# C64-Wifi_UserP.net
KiCad netlist of a schematic drawn in EAGLE
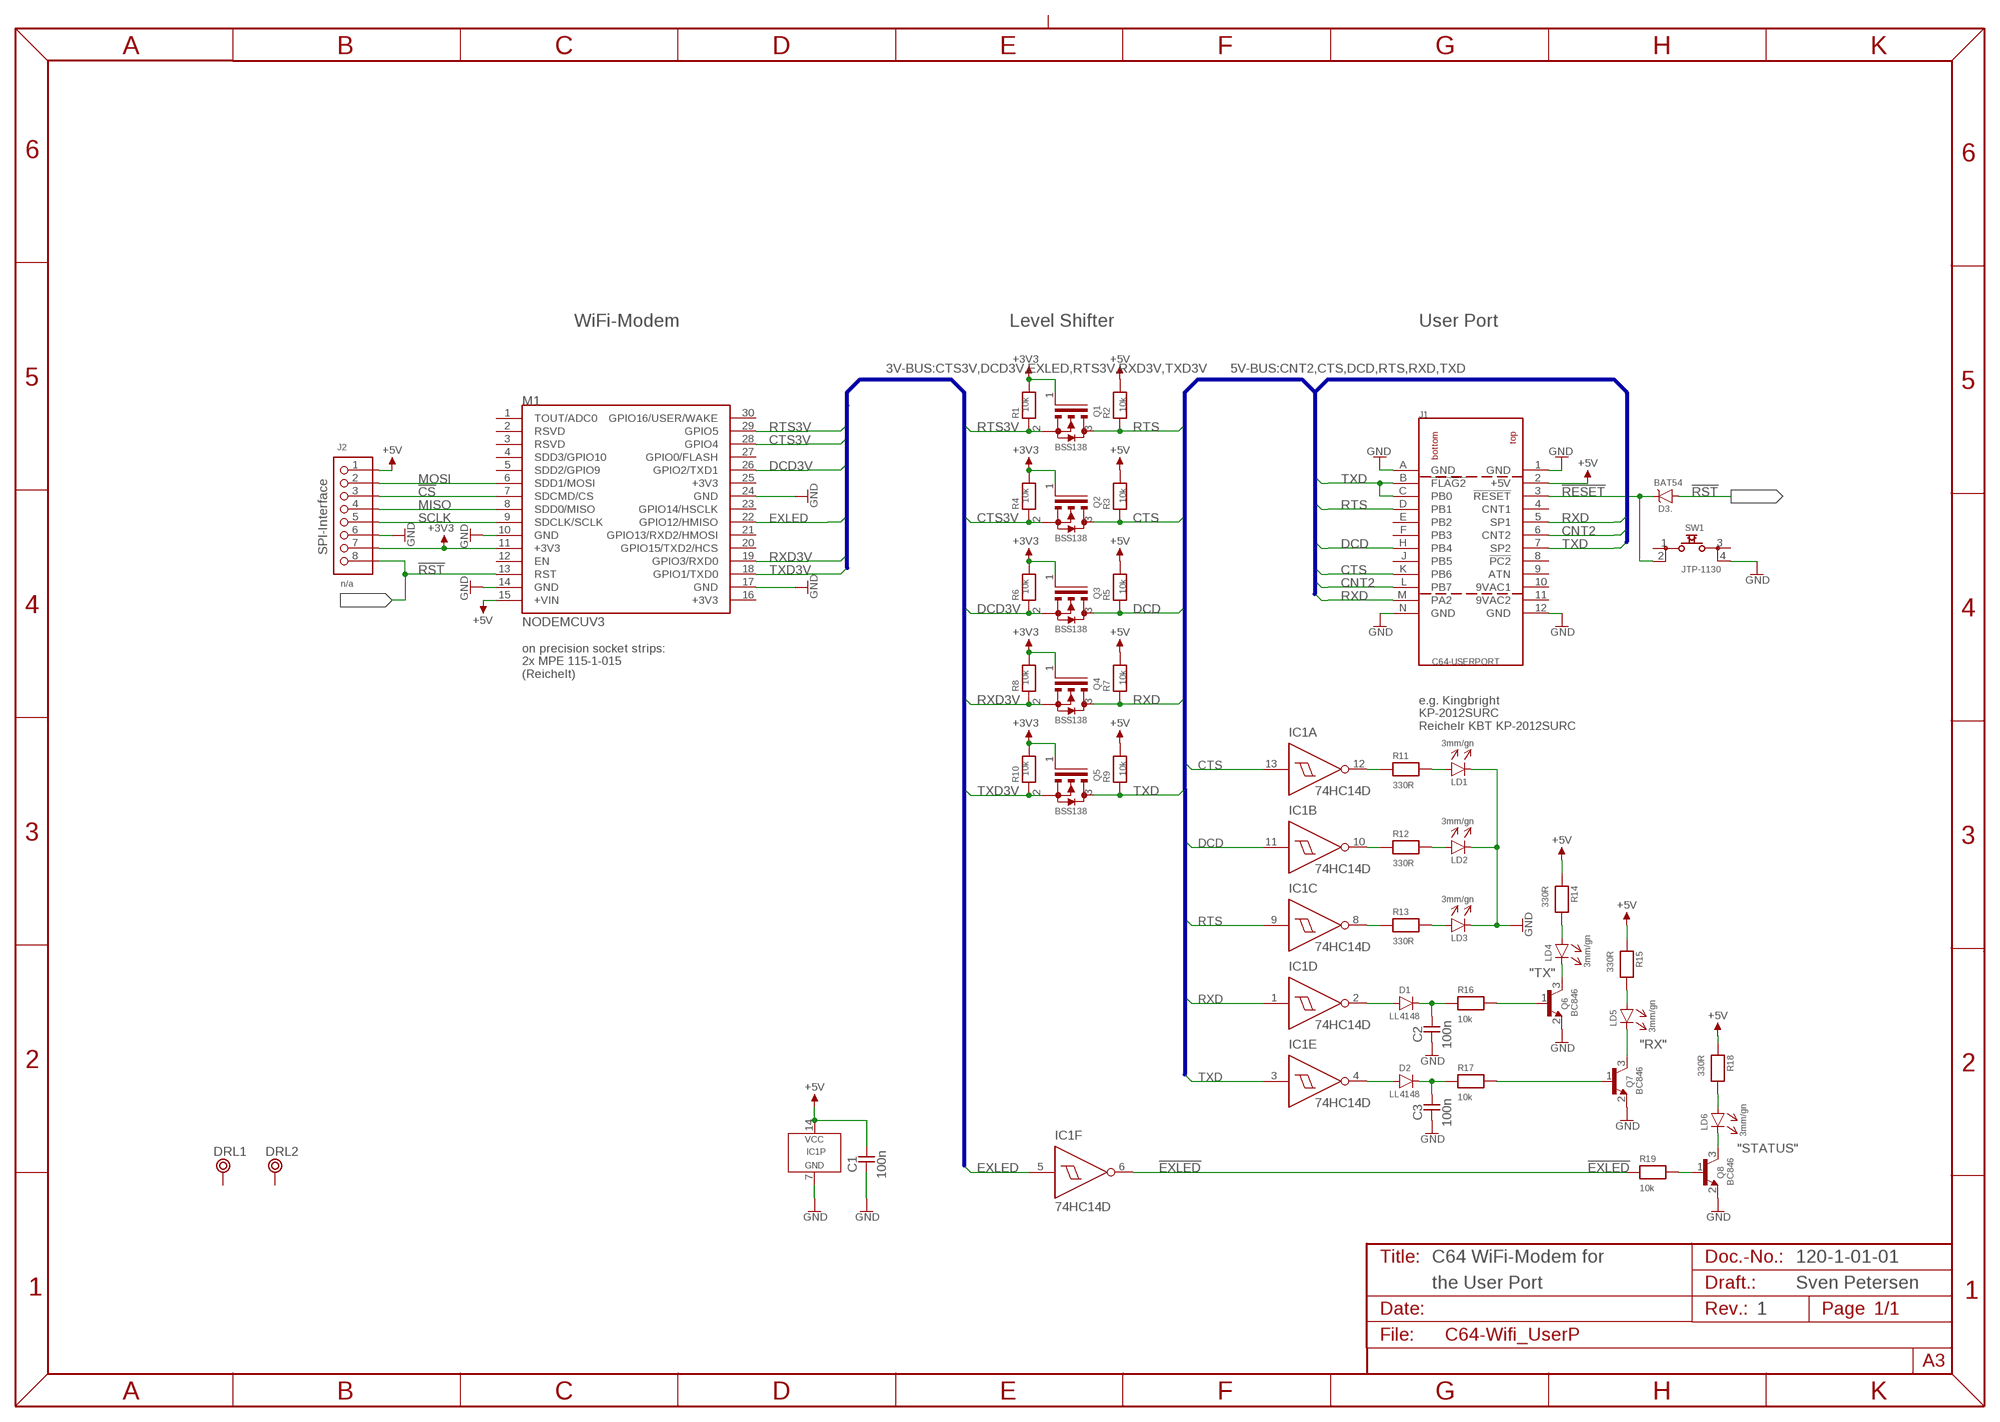
[diagram p0: schematic, sheet 1]

(export (version "E")
  (design (tool "Eeschema 10.0.6"))
  (components
    (comp (ref "C1")
      (value "100n")
      (footprint "eagle-import:0805")
      (libsource (lib "eagle-import") (part "C-0805"))
    )
    (comp (ref "C2")
      (value "100n")
      (footprint "eagle-import:0805")
      (libsource (lib "eagle-import") (part "C-0805"))
    )
    (comp (ref "C3")
      (value "100n")
      (footprint "eagle-import:0805")
      (libsource (lib "eagle-import") (part "C-0805"))
    )
    (comp (ref "D1")
      (value "LL4148")
      (footprint "eagle-import:SOD80C")
      (libsource (lib "eagle-import") (part "LL4148"))
    )
    (comp (ref "D2")
      (value "LL4148")
      (footprint "eagle-import:SOD80C")
      (libsource (lib "eagle-import") (part "LL4148"))
    )
    (comp (ref "D3")
      (value "BAT54")
      (footprint "eagle-import:SOT23")
      (libsource (lib "eagle-import") (part "D-BAT54"))
    )
    (comp (ref "DRL1")
      (value "BOHR3,3")
      (footprint "eagle-import:BOHR3,3")
      (libsource (lib "eagle-import") (part "BOHR3,3"))
    )
    (comp (ref "DRL2")
      (value "BOHR3,3")
      (footprint "eagle-import:BOHR3,3")
      (libsource (lib "eagle-import") (part "BOHR3,3"))
    )
    (comp (ref "IC1")
      (value "74HC14D")
      (footprint "eagle-import:SO-14")
      (libsource (lib "eagle-import") (part "7414"))
    )
    (comp (ref "J1")
      (value "C64-USERPORT")
      (footprint "eagle-import:USERPORT")
      (libsource (lib "eagle-import") (part "C64-USERPORT"))
    )
    (comp (ref "J2")
      (value "n/a")
      (footprint "eagle-import:1X08")
      (libsource (lib "eagle-import") (part "PINHD-1X8"))
    )
    (comp (ref "LD1")
      (value "3mm/gn")
      (footprint "eagle-import:3MM")
      (libsource (lib "eagle-import") (part "0805-LED3MM"))
    )
    (comp (ref "LD2")
      (value "3mm/gn")
      (footprint "eagle-import:3MM")
      (libsource (lib "eagle-import") (part "0805-LED3MM"))
    )
    (comp (ref "LD3")
      (value "3mm/gn")
      (footprint "eagle-import:3MM")
      (libsource (lib "eagle-import") (part "0805-LED3MM"))
    )
    (comp (ref "LD4")
      (value "3mm/gn")
      (footprint "eagle-import:3MM")
      (libsource (lib "eagle-import") (part "0805-LED3MM"))
    )
    (comp (ref "LD5")
      (value "3mm/gn")
      (footprint "eagle-import:3MM")
      (libsource (lib "eagle-import") (part "0805-LED3MM"))
    )
    (comp (ref "LD6")
      (value "3mm/gn")
      (footprint "eagle-import:3MM")
      (libsource (lib "eagle-import") (part "0805-LED3MM"))
    )
    (comp (ref "M1")
      (value "NODEMCUV3")
      (footprint "eagle-import:NODEMCUV3")
      (libsource (lib "eagle-import") (part "NODEMCUV3"))
    )
    (comp (ref "Q1")
      (value "BSS138")
      (footprint "eagle-import:SOT23")
      (libsource (lib "eagle-import") (part "BSS138"))
    )
    (comp (ref "Q2")
      (value "BSS138")
      (footprint "eagle-import:SOT23")
      (libsource (lib "eagle-import") (part "BSS138"))
    )
    (comp (ref "Q3")
      (value "BSS138")
      (footprint "eagle-import:SOT23")
      (libsource (lib "eagle-import") (part "BSS138"))
    )
    (comp (ref "Q4")
      (value "BSS138")
      (footprint "eagle-import:SOT23")
      (libsource (lib "eagle-import") (part "BSS138"))
    )
    (comp (ref "Q5")
      (value "BSS138")
      (footprint "eagle-import:SOT23")
      (libsource (lib "eagle-import") (part "BSS138"))
    )
    (comp (ref "Q6")
      (value "BC846")
      (footprint "eagle-import:SOT23")
      (libsource (lib "eagle-import") (part "BC846"))
    )
    (comp (ref "Q7")
      (value "BC846")
      (footprint "eagle-import:SOT23")
      (libsource (lib "eagle-import") (part "BC846"))
    )
    (comp (ref "Q8")
      (value "BC846")
      (footprint "eagle-import:SOT23")
      (libsource (lib "eagle-import") (part "BC846"))
    )
    (comp (ref "R1")
      (value "10k")
      (footprint "eagle-import:0805")
      (libsource (lib "eagle-import") (part "R-0805"))
    )
    (comp (ref "R2")
      (value "10k")
      (footprint "eagle-import:0805")
      (libsource (lib "eagle-import") (part "R-0805"))
    )
    (comp (ref "R3")
      (value "10k")
      (footprint "eagle-import:0805")
      (libsource (lib "eagle-import") (part "R-0805"))
    )
    (comp (ref "R4")
      (value "10k")
      (footprint "eagle-import:0805")
      (libsource (lib "eagle-import") (part "R-0805"))
    )
    (comp (ref "R5")
      (value "10k")
      (footprint "eagle-import:0805")
      (libsource (lib "eagle-import") (part "R-0805"))
    )
    (comp (ref "R6")
      (value "10k")
      (footprint "eagle-import:0805")
      (libsource (lib "eagle-import") (part "R-0805"))
    )
    (comp (ref "R7")
      (value "10k")
      (footprint "eagle-import:0805")
      (libsource (lib "eagle-import") (part "R-0805"))
    )
    (comp (ref "R8")
      (value "10k")
      (footprint "eagle-import:0805")
      (libsource (lib "eagle-import") (part "R-0805"))
    )
    (comp (ref "R9")
      (value "10k")
      (footprint "eagle-import:0805")
      (libsource (lib "eagle-import") (part "R-0805"))
    )
    (comp (ref "R10")
      (value "10k")
      (footprint "eagle-import:0805")
      (libsource (lib "eagle-import") (part "R-0805"))
    )
    (comp (ref "R11")
      (value "330R")
      (footprint "eagle-import:0805")
      (libsource (lib "eagle-import") (part "R-0805"))
    )
    (comp (ref "R12")
      (value "330R")
      (footprint "eagle-import:0805")
      (libsource (lib "eagle-import") (part "R-0805"))
    )
    (comp (ref "R13")
      (value "330R")
      (footprint "eagle-import:0805")
      (libsource (lib "eagle-import") (part "R-0805"))
    )
    (comp (ref "R14")
      (value "330R")
      (footprint "eagle-import:0805")
      (libsource (lib "eagle-import") (part "R-0805"))
    )
    (comp (ref "R15")
      (value "330R")
      (footprint "eagle-import:0805")
      (libsource (lib "eagle-import") (part "R-0805"))
    )
    (comp (ref "R16")
      (value "10k")
      (footprint "eagle-import:0805")
      (libsource (lib "eagle-import") (part "R-0805"))
    )
    (comp (ref "R17")
      (value "10k")
      (footprint "eagle-import:0805")
      (libsource (lib "eagle-import") (part "R-0805"))
    )
    (comp (ref "R18")
      (value "330R")
      (footprint "eagle-import:0805")
      (libsource (lib "eagle-import") (part "R-0805"))
    )
    (comp (ref "R19")
      (value "10k")
      (footprint "eagle-import:0805")
      (libsource (lib "eagle-import") (part "R-0805"))
    )
    (comp (ref "SW1")
      (value "JTP-1130")
      (footprint "eagle-import:JTP-1130")
      (libsource (lib "eagle-import") (part "JTP-1130"))
    )
  )
  (nets
    (net (code "3") (name "+3V3") (class "Default")
      (node (ref "J2") (pin "7") (pinfunction "7_7") (pintype "passive"))
      (node (ref "M1") (pin "11") (pinfunction "+3V3_11") (pintype "bidirectional"))
      (node (ref "Q1") (pin "1") (pinfunction "G_1") (pintype "bidirectional"))
      (node (ref "Q2") (pin "1") (pinfunction "G_1") (pintype "bidirectional"))
      (node (ref "Q3") (pin "1") (pinfunction "G_1") (pintype "bidirectional"))
      (node (ref "Q4") (pin "1") (pinfunction "G_1") (pintype "bidirectional"))
      (node (ref "Q5") (pin "1") (pinfunction "G_1") (pintype "bidirectional"))
      (node (ref "R1") (pin "2") (pinfunction "2_2") (pintype "passive"))
      (node (ref "R10") (pin "2") (pinfunction "2_2") (pintype "passive"))
      (node (ref "R4") (pin "2") (pinfunction "2_2") (pintype "passive"))
      (node (ref "R6") (pin "2") (pinfunction "2_2") (pintype "passive"))
      (node (ref "R8") (pin "2") (pinfunction "2_2") (pintype "passive"))
    )
    (net (code "4") (name "+5V") (class "Default")
      (node (ref "C1") (pin "2") (pinfunction "2_2") (pintype "passive"))
      (node (ref "IC1") (pin "14") (pinfunction "VCC_14") (pintype "bidirectional"))
      (node (ref "J1") (pin "2") (pinfunction "+5V_2") (pintype "power_in"))
      (node (ref "J2") (pin "1") (pinfunction "1_1") (pintype "passive"))
      (node (ref "M1") (pin "15") (pinfunction "+VIN_15") (pintype "bidirectional"))
      (node (ref "R14") (pin "1") (pinfunction "1_1") (pintype "passive"))
      (node (ref "R15") (pin "1") (pinfunction "1_1") (pintype "passive"))
      (node (ref "R18") (pin "1") (pinfunction "1_1") (pintype "passive"))
      (node (ref "R2") (pin "2") (pinfunction "2_2") (pintype "passive"))
      (node (ref "R3") (pin "2") (pinfunction "2_2") (pintype "passive"))
      (node (ref "R5") (pin "2") (pinfunction "2_2") (pintype "passive"))
      (node (ref "R7") (pin "2") (pinfunction "2_2") (pintype "passive"))
      (node (ref "R9") (pin "2") (pinfunction "2_2") (pintype "passive"))
    )
    (net (code "5") (name "/9VAC1") (class "Default")
      (node (ref "J1") (pin "10") (pinfunction "9VAC1_10") (pintype "power_in"))
    )
    (net (code "6") (name "/9VAC2") (class "Default")
      (node (ref "J1") (pin "11") (pinfunction "9VAC2_11") (pintype "power_in"))
    )
    (net (code "7") (name "/CNT2") (class "Default")
      (node (ref "J1") (pin "6") (pinfunction "CNT2_6") (pintype "input"))
      (node (ref "J1") (pin "L") (pinfunction "PB7_L") (pintype "bidirectional"))
    )
    (net (code "8") (name "/CTS") (class "Default")
      (node (ref "IC1") (pin "13") (pinfunction "I_13") (pintype "input"))
      (node (ref "J1") (pin "K") (pinfunction "PB6_K") (pintype "bidirectional"))
      (node (ref "Q2") (pin "3") (pinfunction "D_3") (pintype "bidirectional"))
      (node (ref "R3") (pin "1") (pinfunction "1_1") (pintype "passive"))
    )
    (net (code "9") (name "/CTS3V") (class "Default")
      (node (ref "M1") (pin "28") (pinfunction "GPIO4_28") (pintype "bidirectional"))
      (node (ref "Q2") (pin "2") (pinfunction "S_2") (pintype "bidirectional"))
      (node (ref "R4") (pin "1") (pinfunction "1_1") (pintype "passive"))
    )
    (net (code "10") (name "/DCD") (class "Default")
      (node (ref "IC1") (pin "11") (pinfunction "I_11") (pintype "input"))
      (node (ref "J1") (pin "H") (pinfunction "PB4_H") (pintype "bidirectional"))
      (node (ref "Q3") (pin "3") (pinfunction "D_3") (pintype "bidirectional"))
      (node (ref "R5") (pin "1") (pinfunction "1_1") (pintype "passive"))
    )
    (net (code "11") (name "/DCD3V") (class "Default")
      (node (ref "M1") (pin "26") (pinfunction "GPIO2/TXD1_26") (pintype "bidirectional"))
      (node (ref "Q3") (pin "2") (pinfunction "S_2") (pintype "bidirectional"))
      (node (ref "R6") (pin "1") (pinfunction "1_1") (pintype "passive"))
    )
    (net (code "12") (name "/EXLED") (class "Default")
      (node (ref "IC1") (pin "5") (pinfunction "I_5") (pintype "input"))
      (node (ref "M1") (pin "22") (pinfunction "GPIO12/HMISO_22") (pintype "bidirectional"))
    )
    (net (code "13") (name "/MISO") (class "Default")
      (node (ref "J2") (pin "4") (pinfunction "4_4") (pintype "passive"))
      (node (ref "M1") (pin "8") (pinfunction "SDD0/MISO_8") (pintype "bidirectional"))
    )
    (net (code "14") (name "/MOSI") (class "Default")
      (node (ref "J2") (pin "2") (pinfunction "2_2") (pintype "passive"))
      (node (ref "M1") (pin "6") (pinfunction "SDD1/MOSI_6") (pintype "bidirectional"))
    )
    (net (code "15") (name "/RTS") (class "Default")
      (node (ref "IC1") (pin "9") (pinfunction "I_9") (pintype "input"))
      (node (ref "J1") (pin "D") (pinfunction "PB1_D") (pintype "bidirectional"))
      (node (ref "Q1") (pin "3") (pinfunction "D_3") (pintype "bidirectional"))
      (node (ref "R2") (pin "1") (pinfunction "1_1") (pintype "passive"))
    )
    (net (code "16") (name "/RTS3V") (class "Default")
      (node (ref "M1") (pin "29") (pinfunction "GPIO5_29") (pintype "bidirectional"))
      (node (ref "Q1") (pin "2") (pinfunction "S_2") (pintype "bidirectional"))
      (node (ref "R1") (pin "1") (pinfunction "1_1") (pintype "passive"))
    )
    (net (code "17") (name "/RXD") (class "Default")
      (node (ref "IC1") (pin "1") (pinfunction "I_1") (pintype "input"))
      (node (ref "J1") (pin "5") (pinfunction "SP1_5") (pintype "bidirectional"))
      (node (ref "J1") (pin "M") (pinfunction "PA2_M") (pintype "bidirectional"))
      (node (ref "Q4") (pin "3") (pinfunction "D_3") (pintype "bidirectional"))
      (node (ref "R7") (pin "1") (pinfunction "1_1") (pintype "passive"))
    )
    (net (code "18") (name "/RXD3V") (class "Default")
      (node (ref "M1") (pin "19") (pinfunction "GPIO3/RXD0_19") (pintype "bidirectional"))
      (node (ref "Q4") (pin "2") (pinfunction "S_2") (pintype "bidirectional"))
      (node (ref "R8") (pin "1") (pinfunction "1_1") (pintype "passive"))
    )
    (net (code "19") (name "/SCLK") (class "Default")
      (node (ref "J2") (pin "5") (pinfunction "5_5") (pintype "passive"))
      (node (ref "M1") (pin "9") (pinfunction "SDCLK/SCLK_9") (pintype "bidirectional"))
    )
    (net (code "20") (name "/TXD") (class "Default")
      (node (ref "IC1") (pin "3") (pinfunction "I_3") (pintype "input"))
      (node (ref "J1") (pin "7") (pinfunction "SP2_7") (pintype "bidirectional"))
      (node (ref "J1") (pin "B") (pinfunction "~{FLAG2}_B") (pintype "input"))
      (node (ref "J1") (pin "C") (pinfunction "PB0_C") (pintype "bidirectional"))
      (node (ref "Q5") (pin "3") (pinfunction "D_3") (pintype "bidirectional"))
      (node (ref "R9") (pin "1") (pinfunction "1_1") (pintype "passive"))
    )
    (net (code "21") (name "/TXD3V") (class "Default")
      (node (ref "M1") (pin "18") (pinfunction "GPIO1/TXD0_18") (pintype "bidirectional"))
      (node (ref "Q5") (pin "2") (pinfunction "S_2") (pintype "bidirectional"))
      (node (ref "R10") (pin "1") (pinfunction "1_1") (pintype "passive"))
    )
    (net (code "24") (name "/~{CS}") (class "Default")
      (node (ref "J2") (pin "3") (pinfunction "3_3") (pintype "passive"))
      (node (ref "M1") (pin "7") (pinfunction "SDCMD/CS_7") (pintype "bidirectional"))
    )
    (net (code "25") (name "/~{EXLED}") (class "Default")
      (node (ref "IC1") (pin "6") (pinfunction "O_6") (pintype "output"))
      (node (ref "R19") (pin "1") (pinfunction "1_1") (pintype "passive"))
    )
    (net (code "26") (name "/~{RESET}") (class "Default")
      (node (ref "D3") (pin "3") (pinfunction "K_3") (pintype "passive"))
      (node (ref "J1") (pin "3") (pinfunction "~{RESET}_3") (pintype "bidirectional"))
      (node (ref "SW1") (pin "2") (pinfunction "2_2") (pintype "passive"))
    )
    (net (code "27") (name "/~{RST}") (class "Default")
      (node (ref "D3") (pin "1") (pinfunction "A_1") (pintype "passive"))
      (node (ref "J2") (pin "8") (pinfunction "8_8") (pintype "passive"))
      (node (ref "M1") (pin "13") (pinfunction "RST_13") (pintype "bidirectional"))
    )
    (net (code "28") (name "GND") (class "Default")
      (node (ref "C1") (pin "1") (pinfunction "1_1") (pintype "passive"))
      (node (ref "C2") (pin "1") (pinfunction "1_1") (pintype "passive"))
      (node (ref "C3") (pin "1") (pinfunction "1_1") (pintype "passive"))
      (node (ref "IC1") (pin "7") (pinfunction "GND_7") (pintype "bidirectional"))
      (node (ref "J1") (pin "1") (pinfunction "GND_1") (pintype "power_in"))
      (node (ref "J1") (pin "12") (pinfunction "GND_12") (pintype "power_in"))
      (node (ref "J1") (pin "A") (pinfunction "GND_A") (pintype "power_in"))
      (node (ref "J1") (pin "N") (pinfunction "GND_N") (pintype "power_in"))
      (node (ref "J2") (pin "6") (pinfunction "6_6") (pintype "passive"))
      (node (ref "LD1") (pin "C") (pinfunction "K_C") (pintype "bidirectional"))
      (node (ref "LD2") (pin "C") (pinfunction "K_C") (pintype "bidirectional"))
      (node (ref "LD3") (pin "C") (pinfunction "K_C") (pintype "bidirectional"))
      (node (ref "M1") (pin "10") (pinfunction "GND_10") (pintype "bidirectional"))
      (node (ref "M1") (pin "14") (pinfunction "GND_14") (pintype "bidirectional"))
      (node (ref "M1") (pin "17") (pinfunction "GND_17") (pintype "bidirectional"))
      (node (ref "M1") (pin "24") (pinfunction "GND_24") (pintype "bidirectional"))
      (node (ref "Q6") (pin "2") (pinfunction "E_2") (pintype "passive"))
      (node (ref "Q7") (pin "2") (pinfunction "E_2") (pintype "passive"))
      (node (ref "Q8") (pin "2") (pinfunction "E_2") (pintype "passive"))
      (node (ref "SW1") (pin "4") (pinfunction "4_4") (pintype "passive"))
    )
    (net (code "29") (name "Net-(C2-Pad2)") (class "Default")
      (node (ref "C2") (pin "2") (pinfunction "2_2") (pintype "passive"))
      (node (ref "D1") (pin "K") (pinfunction "K_K") (pintype "passive"))
      (node (ref "R16") (pin "1") (pinfunction "1_1") (pintype "passive"))
    )
    (net (code "30") (name "Net-(C3-Pad2)") (class "Default")
      (node (ref "C3") (pin "2") (pinfunction "2_2") (pintype "passive"))
      (node (ref "D2") (pin "K") (pinfunction "K_K") (pintype "passive"))
      (node (ref "R17") (pin "1") (pinfunction "1_1") (pintype "passive"))
    )
    (net (code "31") (name "Net-(IC1A-O)") (class "Default")
      (node (ref "IC1") (pin "12") (pinfunction "O_12") (pintype "output"))
      (node (ref "R11") (pin "1") (pinfunction "1_1") (pintype "passive"))
    )
    (net (code "32") (name "Net-(IC1B-O)") (class "Default")
      (node (ref "IC1") (pin "10") (pinfunction "O_10") (pintype "output"))
      (node (ref "R12") (pin "1") (pinfunction "1_1") (pintype "passive"))
    )
    (net (code "33") (name "Net-(IC1C-O)") (class "Default")
      (node (ref "IC1") (pin "8") (pinfunction "O_8") (pintype "output"))
      (node (ref "R13") (pin "1") (pinfunction "1_1") (pintype "passive"))
    )
    (net (code "34") (name "Net-(IC1D-O)") (class "Default")
      (node (ref "D1") (pin "A") (pinfunction "A_A") (pintype "passive"))
      (node (ref "IC1") (pin "2") (pinfunction "O_2") (pintype "output"))
    )
    (net (code "35") (name "Net-(IC1E-O)") (class "Default")
      (node (ref "D2") (pin "A") (pinfunction "A_A") (pintype "passive"))
      (node (ref "IC1") (pin "4") (pinfunction "O_4") (pintype "output"))
    )
    (net (code "36") (name "Net-(LD1-PadA)") (class "Default")
      (node (ref "LD1") (pin "A") (pinfunction "A_A") (pintype "bidirectional"))
      (node (ref "R11") (pin "2") (pinfunction "2_2") (pintype "passive"))
    )
    (net (code "37") (name "Net-(LD2-PadA)") (class "Default")
      (node (ref "LD2") (pin "A") (pinfunction "A_A") (pintype "bidirectional"))
      (node (ref "R12") (pin "2") (pinfunction "2_2") (pintype "passive"))
    )
    (net (code "38") (name "Net-(LD3-PadA)") (class "Default")
      (node (ref "LD3") (pin "A") (pinfunction "A_A") (pintype "bidirectional"))
      (node (ref "R13") (pin "2") (pinfunction "2_2") (pintype "passive"))
    )
    (net (code "39") (name "Net-(LD4-K)") (class "Default")
      (node (ref "LD4") (pin "C") (pinfunction "K_C") (pintype "bidirectional"))
      (node (ref "Q6") (pin "3") (pinfunction "C_3") (pintype "passive"))
    )
    (net (code "40") (name "Net-(LD4-PadA)") (class "Default")
      (node (ref "LD4") (pin "A") (pinfunction "A_A") (pintype "bidirectional"))
      (node (ref "R14") (pin "2") (pinfunction "2_2") (pintype "passive"))
    )
    (net (code "41") (name "Net-(LD5-K)") (class "Default")
      (node (ref "LD5") (pin "C") (pinfunction "K_C") (pintype "bidirectional"))
      (node (ref "Q7") (pin "3") (pinfunction "C_3") (pintype "passive"))
    )
    (net (code "42") (name "Net-(LD5-PadA)") (class "Default")
      (node (ref "LD5") (pin "A") (pinfunction "A_A") (pintype "bidirectional"))
      (node (ref "R15") (pin "2") (pinfunction "2_2") (pintype "passive"))
    )
    (net (code "43") (name "Net-(LD6-K)") (class "Default")
      (node (ref "LD6") (pin "C") (pinfunction "K_C") (pintype "bidirectional"))
      (node (ref "Q8") (pin "3") (pinfunction "C_3") (pintype "passive"))
    )
    (net (code "44") (name "Net-(LD6-PadA)") (class "Default")
      (node (ref "LD6") (pin "A") (pinfunction "A_A") (pintype "bidirectional"))
      (node (ref "R18") (pin "2") (pinfunction "2_2") (pintype "passive"))
    )
    (net (code "45") (name "Net-(Q6-B)") (class "Default")
      (node (ref "Q6") (pin "1") (pinfunction "B_1") (pintype "passive"))
      (node (ref "R16") (pin "2") (pinfunction "2_2") (pintype "passive"))
    )
    (net (code "46") (name "Net-(Q7-B)") (class "Default")
      (node (ref "Q7") (pin "1") (pinfunction "B_1") (pintype "passive"))
      (node (ref "R17") (pin "2") (pinfunction "2_2") (pintype "passive"))
    )
    (net (code "47") (name "Net-(Q8-B)") (class "Default")
      (node (ref "Q8") (pin "1") (pinfunction "B_1") (pintype "passive"))
      (node (ref "R19") (pin "2") (pinfunction "2_2") (pintype "passive"))
    )
    (net (code "48") (name "unconnected-(DRL1-PadP$1)") (class "Default")
      (node (ref "DRL1") (pin "P$1") (pinfunction "P$1_P$1") (pintype "passive"))
    )
    (net (code "49") (name "unconnected-(DRL2-PadP$1)") (class "Default")
      (node (ref "DRL2") (pin "P$1") (pinfunction "P$1_P$1") (pintype "passive"))
    )
    (net (code "50") (name "unconnected-(J1-ATN-Pad9)") (class "Default")
      (node (ref "J1") (pin "9") (pinfunction "ATN_9") (pintype "bidirectional"))
    )
    (net (code "51") (name "unconnected-(J1-CNT1-Pad4)") (class "Default")
      (node (ref "J1") (pin "4") (pinfunction "CNT1_4") (pintype "input"))
    )
    (net (code "52") (name "unconnected-(J1-PB2-PadE)") (class "Default")
      (node (ref "J1") (pin "E") (pinfunction "PB2_E") (pintype "bidirectional"))
    )
    (net (code "53") (name "unconnected-(J1-PB3-PadF)") (class "Default")
      (node (ref "J1") (pin "F") (pinfunction "PB3_F") (pintype "bidirectional"))
    )
    (net (code "54") (name "unconnected-(J1-PB5-PadJ)") (class "Default")
      (node (ref "J1") (pin "J") (pinfunction "PB5_J") (pintype "bidirectional"))
    )
    (net (code "55") (name "unconnected-(J1-~{PC2}-Pad8)") (class "Default")
      (node (ref "J1") (pin "8") (pinfunction "~{PC2}_8") (pintype "bidirectional"))
    )
    (net (code "56") (name "unconnected-(M1-+3V3-Pad16)") (class "Default")
      (node (ref "M1") (pin "16") (pinfunction "+3V3_16") (pintype "bidirectional"))
    )
    (net (code "57") (name "unconnected-(M1-+3V3-Pad25)") (class "Default")
      (node (ref "M1") (pin "25") (pinfunction "+3V3_25") (pintype "bidirectional"))
    )
    (net (code "58") (name "unconnected-(M1-EN-Pad12)") (class "Default")
      (node (ref "M1") (pin "12") (pinfunction "EN_12") (pintype "bidirectional"))
    )
    (net (code "59") (name "unconnected-(M1-GPIO0{slash}FLASH-Pad27)") (class "Default")
      (node (ref "M1") (pin "27") (pinfunction "GPIO0/FLASH_27") (pintype "bidirectional"))
    )
    (net (code "60") (name "unconnected-(M1-GPIO13{slash}RXD2{slash}HMOSI-Pad21)") (class "Default")
      (node (ref "M1") (pin "21") (pinfunction "GPIO13/RXD2/HMOSI_21") (pintype "bidirectional"))
    )
    (net (code "61") (name "unconnected-(M1-GPIO14{slash}HSCLK-Pad23)") (class "Default")
      (node (ref "M1") (pin "23") (pinfunction "GPIO14/HSCLK_23") (pintype "bidirectional"))
    )
    (net (code "62") (name "unconnected-(M1-GPIO15{slash}TXD2{slash}HCS-Pad20)") (class "Default")
      (node (ref "M1") (pin "20") (pinfunction "GPIO15/TXD2/HCS_20") (pintype "bidirectional"))
    )
    (net (code "63") (name "unconnected-(M1-GPIO16{slash}USER{slash}WAKE-Pad30)") (class "Default")
      (node (ref "M1") (pin "30") (pinfunction "GPIO16/USER/WAKE_30") (pintype "bidirectional"))
    )
    (net (code "64") (name "unconnected-(M1-RSVD-Pad2)") (class "Default")
      (node (ref "M1") (pin "2") (pinfunction "RSVD_2") (pintype "bidirectional"))
    )
    (net (code "65") (name "unconnected-(M1-RSVD-Pad3)") (class "Default")
      (node (ref "M1") (pin "3") (pinfunction "RSVD_3") (pintype "bidirectional"))
    )
    (net (code "66") (name "unconnected-(M1-SDD2{slash}GPIO9-Pad5)") (class "Default")
      (node (ref "M1") (pin "5") (pinfunction "SDD2/GPIO9_5") (pintype "bidirectional"))
    )
    (net (code "67") (name "unconnected-(M1-SDD3{slash}GPIO10-Pad4)") (class "Default")
      (node (ref "M1") (pin "4") (pinfunction "SDD3/GPIO10_4") (pintype "bidirectional"))
    )
    (net (code "68") (name "unconnected-(M1-TOUT{slash}ADC0-Pad1)") (class "Default")
      (node (ref "M1") (pin "1") (pinfunction "TOUT/ADC0_1") (pintype "bidirectional"))
    )
    (net (code "69") (name "unconnected-(SW1-Pad1)") (class "Default")
      (node (ref "SW1") (pin "1") (pinfunction "1_1") (pintype "passive"))
    )
    (net (code "70") (name "unconnected-(SW1-Pad3)") (class "Default")
      (node (ref "SW1") (pin "3") (pinfunction "3_3") (pintype "passive"))
    )
  )
)
